# DIP2040.net
KiCad netlist of a schematic drawn in Altium Designer
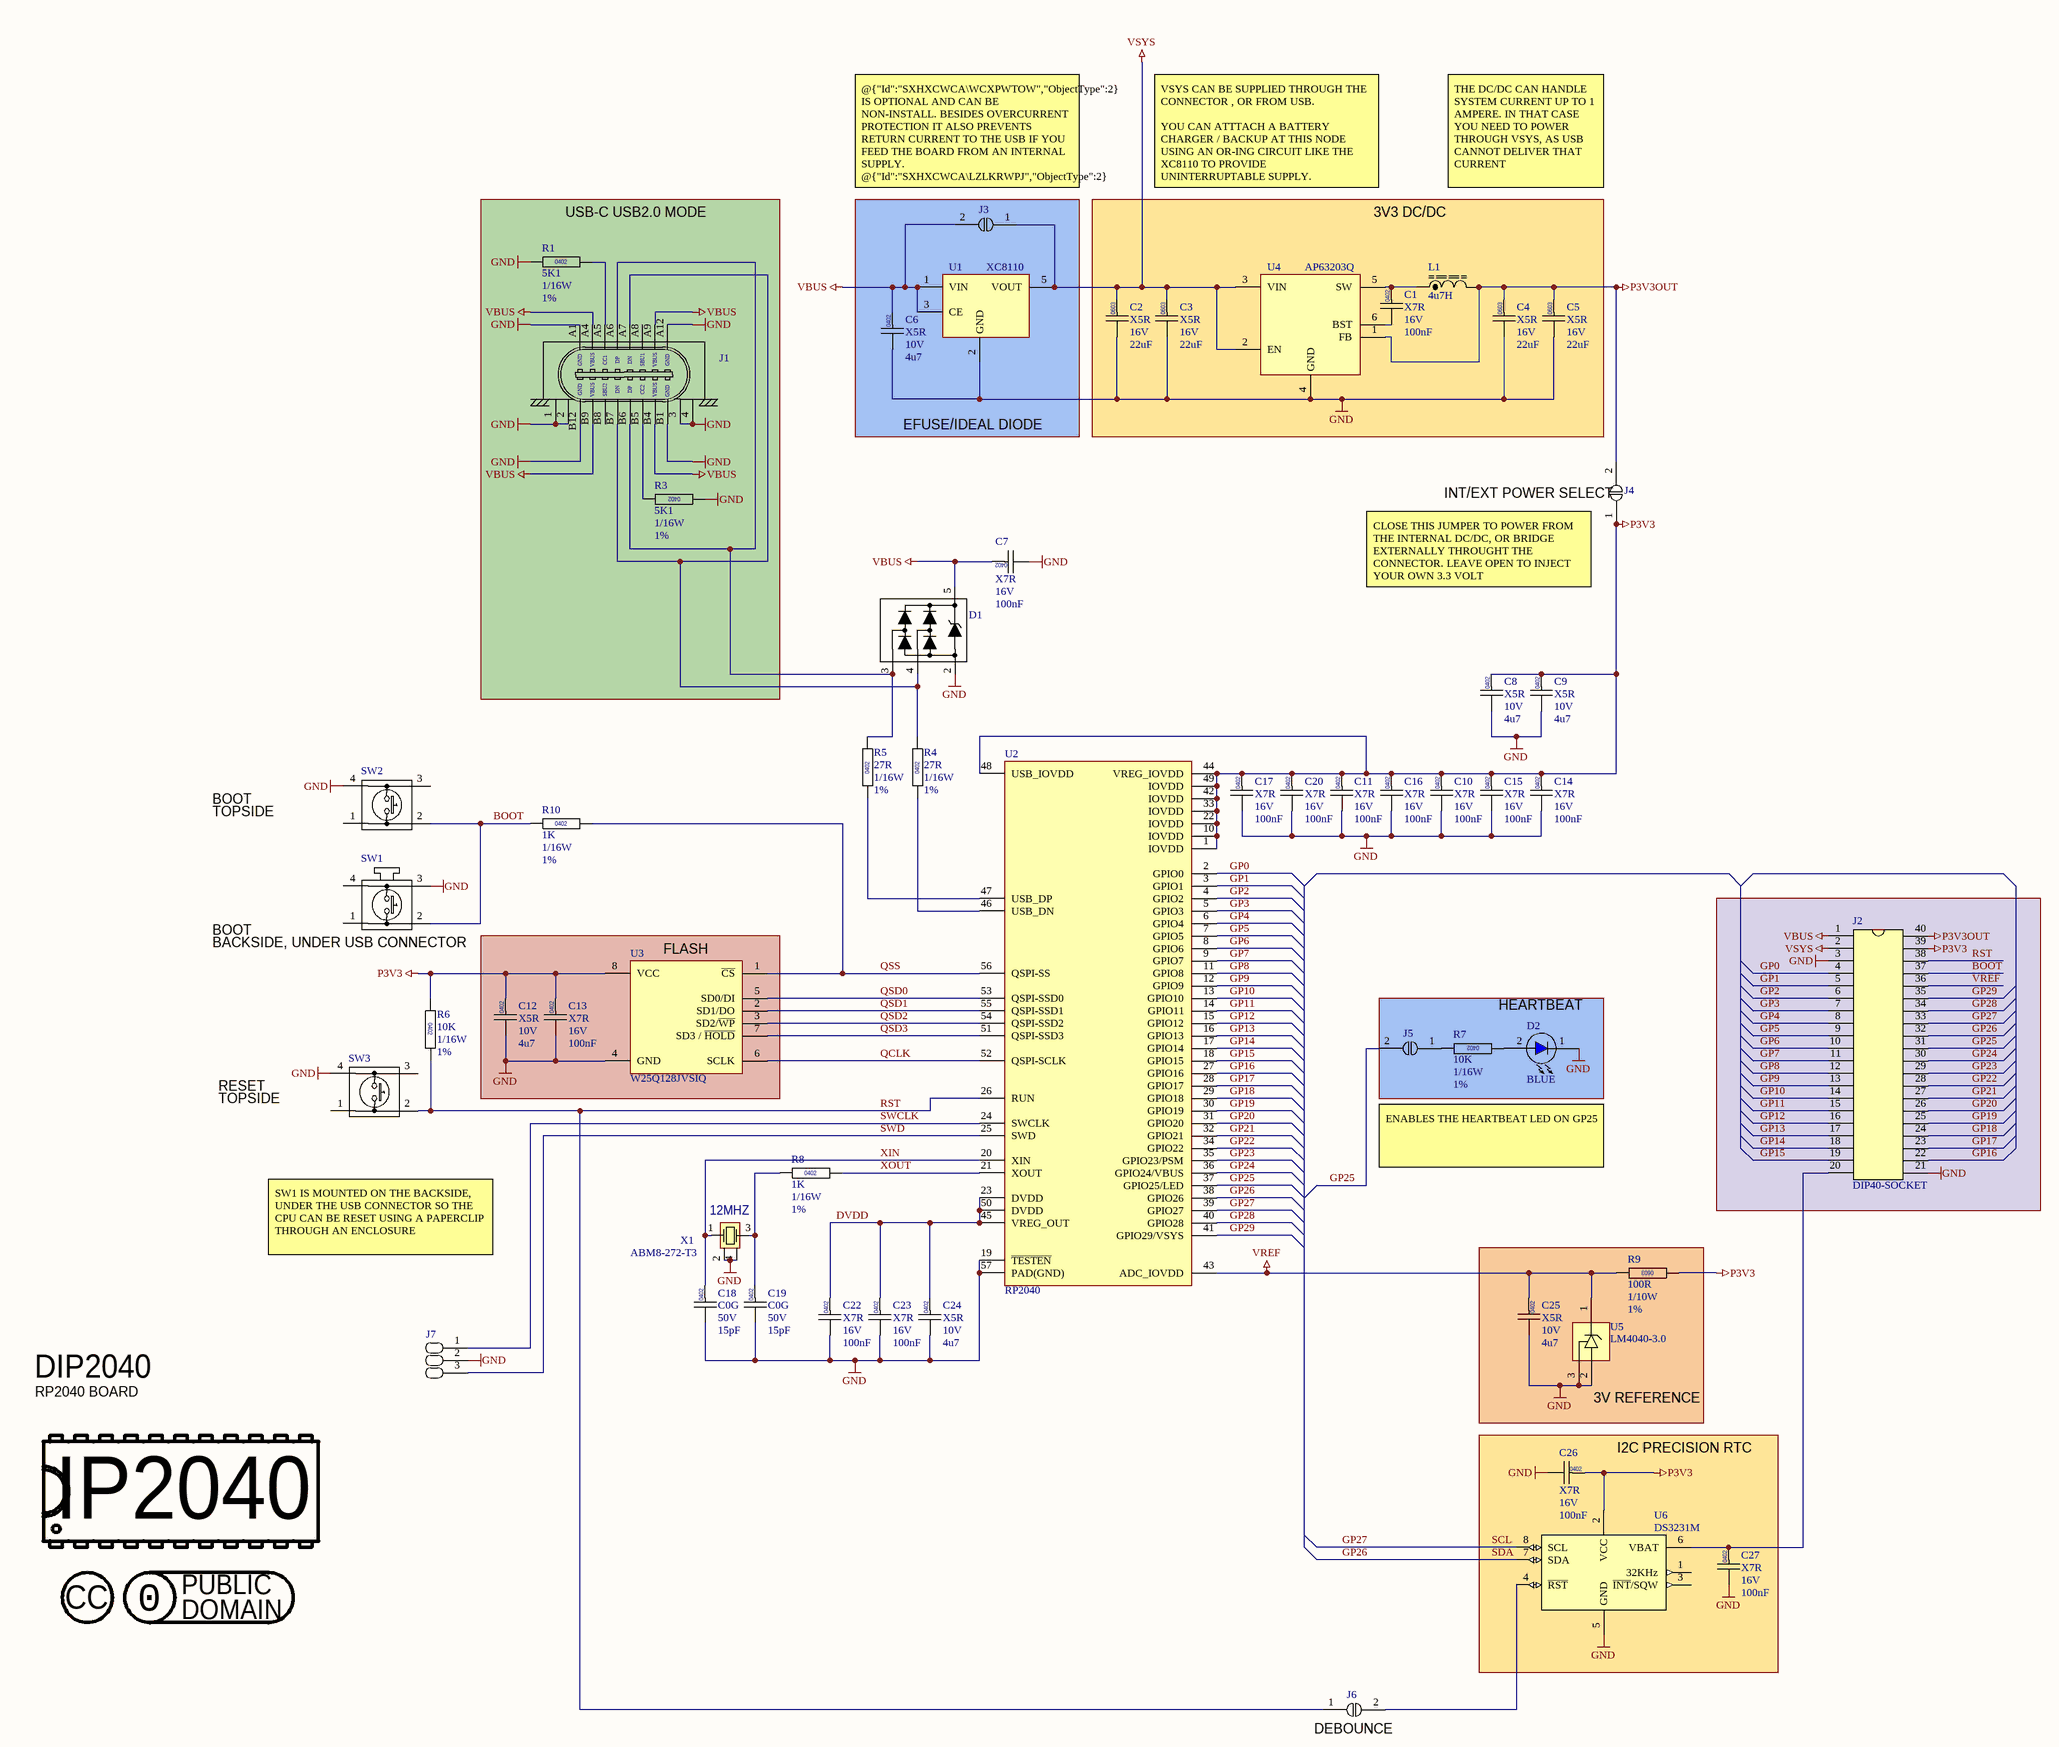
[diagram p0: DIP2040.SchDoc]

(export (version "E")
  (design (tool "Eeschema 10.0.6"))
  (components
    (comp (ref "C1")
      (value "CAP0402")
      (footprint "CAPC0402")
      (description "CAPACITOR,CERAMIC,100nF,16V,X7R,0402")
      (fields
        (field (name "DIELECTRIC") "X7R")
        (field (name "VOLTAGE") "16V")
        (field (name "CAPACITANCE") "100nF")
      )
      (libsource (lib "CAPACITORS") (part "CAPC-0402-100nF-16V-X7R"))
    )
    (comp (ref "C2")
      (value "CAP0603")
      (footprint "CAPC0603")
      (description "CAPACITOR,CERAMIC,22uF,16V,X5R,0603")
      (fields
        (field (name "DIELECTRIC") "X5R")
        (field (name "VOLTAGE") "16V")
        (field (name "CAPACITANCE") "22uF")
      )
      (libsource (lib "CAPACITORS") (part "CAPC-0603-22uF-16V-X5R"))
    )
    (comp (ref "C3")
      (value "CAP0603")
      (footprint "CAPC0603")
      (description "CAPACITOR,CERAMIC,22uF,16V,X5R,0603")
      (fields
        (field (name "DIELECTRIC") "X5R")
        (field (name "VOLTAGE") "16V")
        (field (name "CAPACITANCE") "22uF")
      )
      (libsource (lib "CAPACITORS") (part "CAPC-0603-22uF-16V-X5R"))
    )
    (comp (ref "C4")
      (value "CAP0603")
      (footprint "CAPC0603")
      (description "CAPACITOR,CERAMIC,22uF,16V,X5R,0603")
      (fields
        (field (name "DIELECTRIC") "X5R")
        (field (name "VOLTAGE") "16V")
        (field (name "CAPACITANCE") "22uF")
      )
      (libsource (lib "CAPACITORS") (part "CAPC-0603-22uF-16V-X5R"))
    )
    (comp (ref "C5")
      (value "CAP0603")
      (footprint "CAPC0603")
      (description "CAPACITOR,CERAMIC,22uF,16V,X5R,0603")
      (fields
        (field (name "DIELECTRIC") "X5R")
        (field (name "VOLTAGE") "16V")
        (field (name "CAPACITANCE") "22uF")
      )
      (libsource (lib "CAPACITORS") (part "CAPC-0603-22uF-16V-X5R"))
    )
    (comp (ref "C6")
      (value "CAP0402")
      (footprint "CAPC0402")
      (description "CAPACITOR,CERAMIC,4u7,10V,X5R,0402")
      (fields
        (field (name "DIELECTRIC") "X5R")
        (field (name "VOLTAGE") "10V")
        (field (name "CAPACITANCE") "4u7")
      )
      (libsource (lib "CAPACITORS") (part "CAPC-0402-4u7-10V-X5R"))
    )
    (comp (ref "C7")
      (value "CAP0402")
      (footprint "CAPC0402")
      (description "CAPACITOR,CERAMIC,100nF,16V,X7R,0402")
      (fields
        (field (name "DIELECTRIC") "X7R")
        (field (name "VOLTAGE") "16V")
        (field (name "CAPACITANCE") "100nF")
      )
      (libsource (lib "CAPACITORS") (part "CAPC-0402-100nF-16V-X7R"))
    )
    (comp (ref "C8")
      (value "CAP0402")
      (footprint "CAPC0402")
      (description "CAPACITOR,CERAMIC,4u7,10V,X5R,0402")
      (fields
        (field (name "DIELECTRIC") "X5R")
        (field (name "VOLTAGE") "10V")
        (field (name "CAPACITANCE") "4u7")
      )
      (libsource (lib "CAPACITORS") (part "CAPC-0402-4u7-10V-X5R"))
    )
    (comp (ref "C9")
      (value "CAP0402")
      (footprint "CAPC0402")
      (description "CAPACITOR,CERAMIC,4u7,10V,X5R,0402")
      (fields
        (field (name "DIELECTRIC") "X5R")
        (field (name "VOLTAGE") "10V")
        (field (name "CAPACITANCE") "4u7")
      )
      (libsource (lib "CAPACITORS") (part "CAPC-0402-4u7-10V-X5R"))
    )
    (comp (ref "C10")
      (value "CAP0402")
      (footprint "CAPC0402")
      (description "CAPACITOR,CERAMIC,100nF,16V,X7R,0402")
      (fields
        (field (name "DIELECTRIC") "X7R")
        (field (name "VOLTAGE") "16V")
        (field (name "CAPACITANCE") "100nF")
      )
      (libsource (lib "CAPACITORS") (part "CAPC-0402-100nF-16V-X7R"))
    )
    (comp (ref "C11")
      (value "CAP0402")
      (footprint "CAPC0402")
      (description "CAPACITOR,CERAMIC,100nF,16V,X7R,0402")
      (fields
        (field (name "DIELECTRIC") "X7R")
        (field (name "VOLTAGE") "16V")
        (field (name "CAPACITANCE") "100nF")
      )
      (libsource (lib "CAPACITORS") (part "CAPC-0402-100nF-16V-X7R"))
    )
    (comp (ref "C12")
      (value "CAP0402")
      (footprint "CAPC0402")
      (description "CAPACITOR,CERAMIC,4u7,10V,X5R,0402")
      (fields
        (field (name "DIELECTRIC") "X5R")
        (field (name "VOLTAGE") "10V")
        (field (name "CAPACITANCE") "4u7")
      )
      (libsource (lib "CAPACITORS") (part "CAPC-0402-4u7-10V-X5R"))
    )
    (comp (ref "C13")
      (value "CAP0402")
      (footprint "CAPC0402")
      (description "CAPACITOR,CERAMIC,100nF,16V,X7R,0402")
      (fields
        (field (name "DIELECTRIC") "X7R")
        (field (name "VOLTAGE") "16V")
        (field (name "CAPACITANCE") "100nF")
      )
      (libsource (lib "CAPACITORS") (part "CAPC-0402-100nF-16V-X7R"))
    )
    (comp (ref "C14")
      (value "CAP0402")
      (footprint "CAPC0402")
      (description "CAPACITOR,CERAMIC,100nF,16V,X7R,0402")
      (fields
        (field (name "DIELECTRIC") "X7R")
        (field (name "VOLTAGE") "16V")
        (field (name "CAPACITANCE") "100nF")
      )
      (libsource (lib "CAPACITORS") (part "CAPC-0402-100nF-16V-X7R"))
    )
    (comp (ref "C15")
      (value "CAP0402")
      (footprint "CAPC0402")
      (description "CAPACITOR,CERAMIC,100nF,16V,X7R,0402")
      (fields
        (field (name "DIELECTRIC") "X7R")
        (field (name "VOLTAGE") "16V")
        (field (name "CAPACITANCE") "100nF")
      )
      (libsource (lib "CAPACITORS") (part "CAPC-0402-100nF-16V-X7R"))
    )
    (comp (ref "C16")
      (value "CAP0402")
      (footprint "CAPC0402")
      (description "CAPACITOR,CERAMIC,100nF,16V,X7R,0402")
      (fields
        (field (name "DIELECTRIC") "X7R")
        (field (name "VOLTAGE") "16V")
        (field (name "CAPACITANCE") "100nF")
      )
      (libsource (lib "CAPACITORS") (part "CAPC-0402-100nF-16V-X7R"))
    )
    (comp (ref "C17")
      (value "CAP0402")
      (footprint "CAPC0402")
      (description "CAPACITOR,CERAMIC,100nF,16V,X7R,0402")
      (fields
        (field (name "DIELECTRIC") "X7R")
        (field (name "VOLTAGE") "16V")
        (field (name "CAPACITANCE") "100nF")
      )
      (libsource (lib "CAPACITORS") (part "CAPC-0402-100nF-16V-X7R"))
    )
    (comp (ref "C18")
      (value "CAP0603")
      (footprint "CAPC0402")
      (description "CAPACITOR,CERAMIC,15pF,50V,C0G,0402")
      (fields
        (field (name "DIELECTRIC") "C0G")
        (field (name "VOLTAGE") "50V")
        (field (name "CAPACITANCE") "15pF")
      )
      (libsource (lib "CAPACITORS") (part "CAPC-0402-15PF-50V-C0G"))
    )
    (comp (ref "C19")
      (value "CAP0603")
      (footprint "CAPC0402")
      (description "CAPACITOR,CERAMIC,15pF,50V,C0G,0402")
      (fields
        (field (name "DIELECTRIC") "C0G")
        (field (name "VOLTAGE") "50V")
        (field (name "CAPACITANCE") "15pF")
      )
      (libsource (lib "CAPACITORS") (part "CAPC-0402-15PF-50V-C0G"))
    )
    (comp (ref "C20")
      (value "CAP0402")
      (footprint "CAPC0402")
      (description "CAPACITOR,CERAMIC,100nF,16V,X7R,0402")
      (fields
        (field (name "DIELECTRIC") "X7R")
        (field (name "VOLTAGE") "16V")
        (field (name "CAPACITANCE") "100nF")
      )
      (libsource (lib "CAPACITORS") (part "CAPC-0402-100nF-16V-X7R"))
    )
    (comp (ref "C22")
      (value "CAP0402")
      (footprint "CAPC0402")
      (description "CAPACITOR,CERAMIC,100nF,16V,X7R,0402")
      (fields
        (field (name "DIELECTRIC") "X7R")
        (field (name "VOLTAGE") "16V")
        (field (name "CAPACITANCE") "100nF")
      )
      (libsource (lib "CAPACITORS") (part "CAPC-0402-100nF-16V-X7R"))
    )
    (comp (ref "C23")
      (value "CAP0402")
      (footprint "CAPC0402")
      (description "CAPACITOR,CERAMIC,100nF,16V,X7R,0402")
      (fields
        (field (name "DIELECTRIC") "X7R")
        (field (name "VOLTAGE") "16V")
        (field (name "CAPACITANCE") "100nF")
      )
      (libsource (lib "CAPACITORS") (part "CAPC-0402-100nF-16V-X7R"))
    )
    (comp (ref "C24")
      (value "CAP0402")
      (footprint "CAPC0402")
      (description "CAPACITOR,CERAMIC,4u7,10V,X5R,0402")
      (fields
        (field (name "DIELECTRIC") "X5R")
        (field (name "VOLTAGE") "10V")
        (field (name "CAPACITANCE") "4u7")
      )
      (libsource (lib "CAPACITORS") (part "CAPC-0402-4u7-10V-X5R"))
    )
    (comp (ref "C25")
      (value "CAP0402")
      (footprint "CAPC0402")
      (description "CAPACITOR,CERAMIC,4u7,10V,X5R,0402")
      (fields
        (field (name "DIELECTRIC") "X5R")
        (field (name "VOLTAGE") "10V")
        (field (name "CAPACITANCE") "4u7")
      )
      (libsource (lib "CAPACITORS") (part "CAPC-0402-4u7-10V-X5R"))
    )
    (comp (ref "C26")
      (value "CAP0402")
      (footprint "CAPC0402")
      (description "CAPACITOR,CERAMIC,100nF,16V,X7R,0402")
      (fields
        (field (name "DIELECTRIC") "X7R")
        (field (name "VOLTAGE") "16V")
        (field (name "CAPACITANCE") "100nF")
      )
      (libsource (lib "CAPACITORS") (part "CAPC-0402-100nF-16V-X7R"))
    )
    (comp (ref "C27")
      (value "CAP0402")
      (footprint "CAPC0402")
      (description "CAPACITOR,CERAMIC,100nF,16V,X7R,0402")
      (fields
        (field (name "DIELECTRIC") "X7R")
        (field (name "VOLTAGE") "16V")
        (field (name "CAPACITANCE") "100nF")
      )
      (libsource (lib "CAPACITORS") (part "CAPC-0402-100nF-16V-X7R"))
    )
    (comp (ref "D1")
      (value "TVS-WURTH-824011")
      (footprint "SOT23-5")
      (description "DIODE,TVS,DUAL,UNIDIRECTIONAL,USB")
      (libsource (lib "DIODES") (part "TVS-WURTH-824011"))
    )
    (comp (ref "D2")
      (value "BLUE")
      (footprint "LED-0603-BLUE")
      (description "LED,BLUE,0603")
      (libsource (lib "LED") (part "LED-WURTH-150060BS75000"))
    )
    (comp (ref "J1")
      (value "CONN-USBC-USB2-HOR")
      (footprint "CONN-GCT-USB4085")
      (description "USB-C, RIGHT ANGLE")
      (libsource (lib "CONNECTORS") (part "CONN-USBC-USB2-HOR"))
    )
    (comp (ref "J2")
      (value "DIP40-SOCKET")
      (footprint "CONN-DIP40-SOCKET")
      (libsource (lib "IC-I2C") (part "DIP40-SOCKET"))
    )
    (comp (ref "J3")
      (value "SOLDERPAD-2")
      (footprint "SOLDERPAD-2")
      (libsource (lib "BOARDFEATURES") (part "SOLDERPAD-2"))
    )
    (comp (ref "J4")
      (value "SOLDERPAD-2")
      (footprint "SOLDERPAD-2")
      (libsource (lib "BOARDFEATURES") (part "SOLDERPAD-2"))
    )
    (comp (ref "J5")
      (value "SOLDERPAD-2")
      (footprint "SOLDERPAD-2")
      (libsource (lib "BOARDFEATURES") (part "SOLDERPAD-2"))
    )
    (comp (ref "J6")
      (value "SOLDERPAD-2")
      (footprint "SOLDERPAD-2")
      (libsource (lib "BOARDFEATURES") (part "SOLDERPAD-2"))
    )
    (comp (ref "J7")
      (value "CONN-TESTPAD-1.5X1-2MMP-3")
      (footprint "CONN-TESTPAD-1.5X1-2MMP-3")
      (libsource (lib "CONNECTORS") (part "CONN-TESTPAD-1.5X1-2MMP-3"))
    )
    (comp (ref "L1")
      (value "4u7H")
      (footprint "IND-ABRACON-ASPI-3012S-3R9N-T")
      (description "IND,4.7uH,1.06A,3X3, NRH3012T4R7MN")
      (fields (field (name "Comment") "4.7uH"))
      (libsource (lib "INDUCTORS") (part "IND-TAIYO-NRH3012T4R7MN"))
    )
    (comp (ref "LOGO1")
      (value "LOGO-LICENSE-CC0-PUBLIC")
      (footprint "LOGO-LICENSE-CC0-PUBLIC")
      (libsource (lib "LOGO") (part "LOGO-LICENSE-CC0-PUBLIC"))
    )
    (comp (ref "LOGO2")
      (value "LOGO-LICENSE-CC")
      (footprint "LOGO-LICENSE-CC")
      (libsource (lib "LOGO") (part "LOGO-LICENSE-CC"))
    )
    (comp (ref "R1")
      (value "5K1")
      (footprint "RESC0402")
      (description "RESISTOR,5K1,1%,63mW,0402 (1005)")
      (fields
        (field (name "POWER") "1/16W")
        (field (name "TOLERANCE") "1%")
        (field (name "Comment") "RESC0402")
      )
      (libsource (lib "RESISTORS") (part "RESC-0402-5K1-1%-1/10W"))
    )
    (comp (ref "R3")
      (value "5K1")
      (footprint "RESC0402")
      (description "RESISTOR,5K1,1%,63mW,0402 (1005)")
      (fields
        (field (name "POWER") "1/16W")
        (field (name "TOLERANCE") "1%")
        (field (name "Comment") "RESC0402")
      )
      (libsource (lib "RESISTORS") (part "RESC-0402-5K1-1%-1/10W"))
    )
    (comp (ref "R4")
      (value "27R")
      (footprint "RESC0402")
      (description "RESISTOR,27R,1%,63mW,0402 (1005)")
      (fields
        (field (name "POWER") "1/16W")
        (field (name "TOLERANCE") "1%")
        (field (name "Comment") "RESC0402")
      )
      (libsource (lib "RESISTORS") (part "RESC-0402-27R-1%-1/10W"))
    )
    (comp (ref "R5")
      (value "27R")
      (footprint "RESC0402")
      (description "RESISTOR,27R,1%,63mW,0402 (1005)")
      (fields
        (field (name "POWER") "1/16W")
        (field (name "TOLERANCE") "1%")
        (field (name "Comment") "RESC0402")
      )
      (libsource (lib "RESISTORS") (part "RESC-0402-27R-1%-1/10W"))
    )
    (comp (ref "R6")
      (value "10K")
      (footprint "RESC0402")
      (description "RESISTOR,10K,1%,63mW,0402 (1005)")
      (fields
        (field (name "POWER") "1/16W")
        (field (name "TOLERANCE") "1%")
        (field (name "Comment") "RESC0402")
      )
      (libsource (lib "RESISTORS") (part "RESC-0402-10K-1%-1/10W"))
    )
    (comp (ref "R7")
      (value "10K")
      (footprint "RESC0402")
      (description "RESISTOR,10K,1%,63mW,0402 (1005)")
      (fields
        (field (name "POWER") "1/16W")
        (field (name "TOLERANCE") "1%")
        (field (name "Comment") "RESC0402")
      )
      (libsource (lib "RESISTORS") (part "RESC-0402-10K-1%-1/10W"))
    )
    (comp (ref "R8")
      (value "1K")
      (footprint "RESC0402")
      (description "RESISTOR,1K,1%,63mW,0402 (1005)")
      (fields
        (field (name "POWER") "1/16W")
        (field (name "TOLERANCE") "1%")
        (field (name "Comment") "RESC0402")
      )
      (libsource (lib "RESISTORS") (part "RESC-0402-1K-1%-1/10W"))
    )
    (comp (ref "R9")
      (value "100R")
      (footprint "RES0603")
      (description "RESISTOR,100R,1%,100mW,0603 (1608)")
      (fields
        (field (name "POWER") "1/10W")
        (field (name "TOLERANCE") "1%")
        (field (name "Comment") "RESC0603")
      )
      (libsource (lib "RESISTORS") (part "RESC-0603-100R-1%-1/10W"))
    )
    (comp (ref "R10")
      (value "1K")
      (footprint "RESC0402")
      (description "RESISTOR,1K,1%,63mW,0402 (1005)")
      (fields
        (field (name "POWER") "1/16W")
        (field (name "TOLERANCE") "1%")
        (field (name "Comment") "RESC0402")
      )
      (libsource (lib "RESISTORS") (part "RESC-0402-1K-1%-1/10W"))
    )
    (comp (ref "SW1")
      (value "SWITCH-E-SWITCH-TL1016")
      (footprint "SWITCH-ESWITCH-TL1016")
      (libsource (lib "SWITCH") (part "SWITCH-E-SWITCH-TL1016"))
    )
    (comp (ref "SW2")
      (value "SWITCH-PANASONIC-EVP-AA202K")
      (footprint "SWITCH-PANASONIC-EVP-AA202K")
      (libsource (lib "SWITCH") (part "SWITCH-PANASONIC-EVP-AA202K"))
    )
    (comp (ref "SW3")
      (value "SWITCH-PANASONIC-EVP-AA202K")
      (footprint "SWITCH-PANASONIC-EVP-AA202K")
      (libsource (lib "SWITCH") (part "SWITCH-PANASONIC-EVP-AA202K"))
    )
    (comp (ref "U1")
      (value "XC8110")
      (footprint "SOT23-5")
      (description "IC,PMIC,IDEAL DIODE ORING CONTROLLER")
      (libsource (lib "IC-REG") (part "IC-TOREX-XC8110"))
    )
    (comp (ref "U2")
      (value "RP2040")
      (footprint "QFN40P700X700X90-56N-TH310X310")
      (libsource (lib "IC-CPU") (part "IC-RPI-RP2040-DIP40"))
    )
    (comp (ref "U3")
      (value "W25Q128JVSIQ")
      (footprint "SO127P790-8N")
      (description "IC,FLASH,QSPI,16Mx8")
      (libsource (lib "IC-SPI") (part "IC-WINBOND-W25Q128JVSIQ"))
    )
    (comp (ref "U4")
      (value "AP63203Q")
      (footprint "SOT23-6")
      (description "IC,PMIC,STEP-DOWN, 2A 3.3V")
      (libsource (lib "IC-REG") (part "IC-DIODES-AP63203Q"))
    )
    (comp (ref "U5")
      (value "LM4040-3.0")
      (footprint "SOT23")
      (description "IC,VOLTAGE REFERENCE,3.0V")
      (libsource (lib "IC-REG") (part "IC-TI-LM4040-3"))
    )
    (comp (ref "U6")
      (value "DS3231M")
      (footprint "SO127P600-8N")
      (description "IC,RTC,I2C,DS3231M")
      (libsource (lib "IC-I2C") (part "IC-ANALOG-DS3231M"))
    )
    (comp (ref "X1")
      (value "ABM8-272-T3")
      (footprint "XTAL-ABRACON-ABM8-272-T3")
      (description "XTAL,12MHZ,RP2350")
      (libsource (lib "CRYSTALS") (part "XTAL-ABRACON-ABM8-272-T3"))
    )
  )
  (nets
    (net (code "1") (name "/BOOT") (class "Default")
      (node (ref "J2") (pin "37") (pinfunction "37_37") (pintype "passive"))
      (node (ref "R10") (pin "1") (pintype "passive"))
      (node (ref "SW1") (pin "2") (pinfunction "2_2") (pintype "passive"))
      (node (ref "SW2") (pin "2") (pinfunction "2_2") (pintype "passive"))
    )
    (net (code "2") (name "/DVDD") (class "Default")
      (node (ref "C22") (pin "1") (pintype "passive"))
      (node (ref "C23") (pin "1") (pintype "passive"))
      (node (ref "C24") (pin "1") (pintype "passive"))
      (node (ref "U2") (pin "23") (pinfunction "DVDD_23") (pintype "passive"))
      (node (ref "U2") (pin "45") (pinfunction "VREG_OUT_45") (pintype "passive"))
      (node (ref "U2") (pin "50") (pinfunction "DVDD_50") (pintype "passive"))
    )
    (net (code "3") (name "/GP0") (class "Default")
      (node (ref "J2") (pin "4") (pinfunction "4_4") (pintype "passive"))
      (node (ref "U2") (pin "2") (pinfunction "GPIO0_2") (pintype "passive"))
    )
    (net (code "4") (name "/GP1") (class "Default")
      (node (ref "J2") (pin "5") (pinfunction "5_5") (pintype "passive"))
      (node (ref "U2") (pin "3") (pinfunction "GPIO1_3") (pintype "passive"))
    )
    (net (code "5") (name "/GP2") (class "Default")
      (node (ref "J2") (pin "6") (pinfunction "6_6") (pintype "passive"))
      (node (ref "U2") (pin "4") (pinfunction "GPIO2_4") (pintype "passive"))
    )
    (net (code "6") (name "/GP3") (class "Default")
      (node (ref "J2") (pin "7") (pinfunction "7_7") (pintype "passive"))
      (node (ref "U2") (pin "5") (pinfunction "GPIO3_5") (pintype "passive"))
    )
    (net (code "7") (name "/GP4") (class "Default")
      (node (ref "J2") (pin "8") (pinfunction "8_8") (pintype "passive"))
      (node (ref "U2") (pin "6") (pinfunction "GPIO4_6") (pintype "passive"))
    )
    (net (code "8") (name "/GP5") (class "Default")
      (node (ref "J2") (pin "9") (pinfunction "9_9") (pintype "passive"))
      (node (ref "U2") (pin "7") (pinfunction "GPIO5_7") (pintype "passive"))
    )
    (net (code "9") (name "/GP6") (class "Default")
      (node (ref "J2") (pin "10") (pinfunction "10_10") (pintype "passive"))
      (node (ref "U2") (pin "8") (pinfunction "GPIO6_8") (pintype "passive"))
    )
    (net (code "10") (name "/GP7") (class "Default")
      (node (ref "J2") (pin "11") (pinfunction "11_11") (pintype "passive"))
      (node (ref "U2") (pin "9") (pinfunction "GPIO7_9") (pintype "passive"))
    )
    (net (code "11") (name "/GP8") (class "Default")
      (node (ref "J2") (pin "12") (pinfunction "12_12") (pintype "passive"))
      (node (ref "U2") (pin "11") (pinfunction "GPIO8_11") (pintype "passive"))
    )
    (net (code "12") (name "/GP9") (class "Default")
      (node (ref "J2") (pin "13") (pinfunction "13_13") (pintype "passive"))
      (node (ref "U2") (pin "12") (pinfunction "GPIO9_12") (pintype "passive"))
    )
    (net (code "13") (name "/GP10") (class "Default")
      (node (ref "J2") (pin "14") (pinfunction "14_14") (pintype "passive"))
      (node (ref "U2") (pin "13") (pinfunction "GPIO10_13") (pintype "passive"))
    )
    (net (code "14") (name "/GP11") (class "Default")
      (node (ref "J2") (pin "15") (pinfunction "15_15") (pintype "passive"))
      (node (ref "U2") (pin "14") (pinfunction "GPIO11_14") (pintype "passive"))
    )
    (net (code "15") (name "/GP12") (class "Default")
      (node (ref "J2") (pin "16") (pinfunction "16_16") (pintype "passive"))
      (node (ref "U2") (pin "15") (pinfunction "GPIO12_15") (pintype "passive"))
    )
    (net (code "16") (name "/GP13") (class "Default")
      (node (ref "J2") (pin "17") (pinfunction "17_17") (pintype "passive"))
      (node (ref "U2") (pin "16") (pinfunction "GPIO13_16") (pintype "passive"))
    )
    (net (code "17") (name "/GP14") (class "Default")
      (node (ref "J2") (pin "18") (pinfunction "18_18") (pintype "passive"))
      (node (ref "U2") (pin "17") (pinfunction "GPIO14_17") (pintype "passive"))
    )
    (net (code "18") (name "/GP15") (class "Default")
      (node (ref "J2") (pin "19") (pinfunction "19_19") (pintype "passive"))
      (node (ref "U2") (pin "18") (pinfunction "GPIO15_18") (pintype "passive"))
    )
    (net (code "19") (name "/GP16") (class "Default")
      (node (ref "J2") (pin "22") (pinfunction "22_22") (pintype "passive"))
      (node (ref "U2") (pin "27") (pinfunction "GPIO16_27") (pintype "passive"))
    )
    (net (code "20") (name "/GP17") (class "Default")
      (node (ref "J2") (pin "23") (pinfunction "23_23") (pintype "passive"))
      (node (ref "U2") (pin "28") (pinfunction "GPIO17_28") (pintype "passive"))
    )
    (net (code "21") (name "/GP18") (class "Default")
      (node (ref "J2") (pin "24") (pinfunction "24_24") (pintype "passive"))
      (node (ref "U2") (pin "29") (pinfunction "GPIO18_29") (pintype "passive"))
    )
    (net (code "22") (name "/GP19") (class "Default")
      (node (ref "J2") (pin "25") (pinfunction "25_25") (pintype "passive"))
      (node (ref "U2") (pin "30") (pinfunction "GPIO19_30") (pintype "passive"))
    )
    (net (code "23") (name "/GP20") (class "Default")
      (node (ref "J2") (pin "26") (pinfunction "26_26") (pintype "passive"))
      (node (ref "U2") (pin "31") (pinfunction "GPIO20_31") (pintype "passive"))
    )
    (net (code "24") (name "/GP21") (class "Default")
      (node (ref "J2") (pin "27") (pinfunction "27_27") (pintype "passive"))
      (node (ref "U2") (pin "32") (pinfunction "GPIO21_32") (pintype "passive"))
    )
    (net (code "25") (name "/GP22") (class "Default")
      (node (ref "J2") (pin "28") (pinfunction "28_28") (pintype "passive"))
      (node (ref "U2") (pin "34") (pinfunction "GPIO22_34") (pintype "passive"))
    )
    (net (code "26") (name "/GP23") (class "Default")
      (node (ref "J2") (pin "29") (pinfunction "29_29") (pintype "passive"))
      (node (ref "U2") (pin "35") (pinfunction "GPIO23/PSM_35") (pintype "passive"))
    )
    (net (code "27") (name "/GP24") (class "Default")
      (node (ref "J2") (pin "30") (pinfunction "30_30") (pintype "passive"))
      (node (ref "U2") (pin "36") (pinfunction "GPIO24/VBUS_36") (pintype "passive"))
    )
    (net (code "28") (name "/GP25") (class "Default")
      (node (ref "J2") (pin "31") (pinfunction "31_31") (pintype "passive"))
      (node (ref "J5") (pin "2") (pinfunction "2_2") (pintype "passive"))
      (node (ref "U2") (pin "37") (pinfunction "GPIO25/LED_37") (pintype "passive"))
    )
    (net (code "29") (name "/GP26") (class "Default")
      (node (ref "J2") (pin "32") (pinfunction "32_32") (pintype "passive"))
      (node (ref "U2") (pin "38") (pinfunction "GPIO26_38") (pintype "passive"))
      (node (ref "U6") (pin "7") (pinfunction "SDA_7") (pintype "bidirectional"))
    )
    (net (code "30") (name "/GP27") (class "Default")
      (node (ref "J2") (pin "33") (pinfunction "33_33") (pintype "passive"))
      (node (ref "U2") (pin "39") (pinfunction "GPIO27_39") (pintype "passive"))
      (node (ref "U6") (pin "8") (pinfunction "SCL_8") (pintype "bidirectional"))
    )
    (net (code "31") (name "/GP28") (class "Default")
      (node (ref "J2") (pin "34") (pinfunction "34_34") (pintype "passive"))
      (node (ref "U2") (pin "40") (pinfunction "GPIO28_40") (pintype "passive"))
    )
    (net (code "32") (name "/GP29") (class "Default")
      (node (ref "J2") (pin "35") (pinfunction "35_35") (pintype "passive"))
      (node (ref "U2") (pin "41") (pinfunction "GPIO29/VSYS_41") (pintype "passive"))
    )
    (net (code "33") (name "/QCLK") (class "Default")
      (node (ref "U2") (pin "52") (pinfunction "QSPI-SCLK_52") (pintype "passive"))
      (node (ref "U3") (pin "6") (pinfunction "SCLK_6") (pintype "passive"))
    )
    (net (code "34") (name "/QSD0") (class "Default")
      (node (ref "U2") (pin "53") (pinfunction "QSPI-SSD0_53") (pintype "passive"))
      (node (ref "U3") (pin "5") (pinfunction "SD0/DI_5") (pintype "passive"))
    )
    (net (code "35") (name "/QSD1") (class "Default")
      (node (ref "U2") (pin "55") (pinfunction "QSPI-SSD1_55") (pintype "passive"))
      (node (ref "U3") (pin "2") (pinfunction "SD1/DO_2") (pintype "passive"))
    )
    (net (code "36") (name "/QSD2") (class "Default")
      (node (ref "U2") (pin "54") (pinfunction "QSPI-SSD2_54") (pintype "passive"))
      (node (ref "U3") (pin "3") (pinfunction "SD2/~{WP}_3") (pintype "passive"))
    )
    (net (code "37") (name "/QSD3") (class "Default")
      (node (ref "U2") (pin "51") (pinfunction "QSPI-SSD3_51") (pintype "passive"))
      (node (ref "U3") (pin "7") (pinfunction "SD3_/_~{HOLD}_7") (pintype "passive"))
    )
    (net (code "38") (name "/QSS") (class "Default")
      (node (ref "R10") (pin "2") (pintype "passive"))
      (node (ref "U2") (pin "56") (pinfunction "QSPI-SS_56") (pintype "passive"))
      (node (ref "U3") (pin "1") (pinfunction "~{CS}_1") (pintype "passive"))
    )
    (net (code "39") (name "/RST") (class "Default")
      (node (ref "J2") (pin "38") (pinfunction "38_38") (pintype "passive"))
      (node (ref "J6") (pin "1") (pinfunction "1_1") (pintype "passive"))
      (node (ref "R6") (pin "1") (pintype "passive"))
      (node (ref "SW3") (pin "2") (pinfunction "2_2") (pintype "passive"))
      (node (ref "U2") (pin "26") (pinfunction "RUN_26") (pintype "passive"))
    )
    (net (code "40") (name "/SWCLK") (class "Default")
      (node (ref "J7") (pin "1") (pinfunction "1_1") (pintype "passive"))
      (node (ref "U2") (pin "24") (pinfunction "SWCLK_24") (pintype "passive"))
    )
    (net (code "41") (name "/SWD") (class "Default")
      (node (ref "J7") (pin "3") (pinfunction "3_3") (pintype "passive"))
      (node (ref "U2") (pin "25") (pinfunction "SWD_25") (pintype "passive"))
    )
    (net (code "42") (name "/XIN") (class "Default")
      (node (ref "C18") (pin "1") (pintype "passive"))
      (node (ref "U2") (pin "20") (pinfunction "XIN_20") (pintype "passive"))
      (node (ref "X1") (pin "1") (pinfunction "1_1") (pintype "passive"))
    )
    (net (code "43") (name "/XOUT") (class "Default")
      (node (ref "R8") (pin "2") (pintype "passive"))
      (node (ref "U2") (pin "21") (pinfunction "XOUT_21") (pintype "passive"))
    )
    (net (code "44") (name "GND") (class "Default")
      (node (ref "C10") (pin "2") (pintype "passive"))
      (node (ref "C11") (pin "2") (pintype "passive"))
      (node (ref "C12") (pin "2") (pintype "passive"))
      (node (ref "C13") (pin "2") (pintype "passive"))
      (node (ref "C14") (pin "2") (pintype "passive"))
      (node (ref "C15") (pin "2") (pintype "passive"))
      (node (ref "C16") (pin "2") (pintype "passive"))
      (node (ref "C17") (pin "2") (pintype "passive"))
      (node (ref "C18") (pin "2") (pintype "passive"))
      (node (ref "C19") (pin "2") (pintype "passive"))
      (node (ref "C2") (pin "2") (pintype "passive"))
      (node (ref "C20") (pin "2") (pintype "passive"))
      (node (ref "C22") (pin "2") (pintype "passive"))
      (node (ref "C23") (pin "2") (pintype "passive"))
      (node (ref "C24") (pin "2") (pintype "passive"))
      (node (ref "C25") (pin "2") (pintype "passive"))
      (node (ref "C26") (pin "2") (pintype "passive"))
      (node (ref "C27") (pin "2") (pintype "passive"))
      (node (ref "C3") (pin "2") (pintype "passive"))
      (node (ref "C4") (pin "2") (pintype "passive"))
      (node (ref "C5") (pin "2") (pintype "passive"))
      (node (ref "C6") (pin "2") (pintype "passive"))
      (node (ref "C7") (pin "2") (pintype "passive"))
      (node (ref "C8") (pin "2") (pintype "passive"))
      (node (ref "C9") (pin "2") (pintype "passive"))
      (node (ref "D1") (pin "2") (pinfunction "A_2") (pintype "passive"))
      (node (ref "D2") (pin "1") (pinfunction "A_1") (pintype "passive"))
      (node (ref "J1") (pin "1") (pinfunction "1_1") (pintype "passive"))
      (node (ref "J1") (pin "2") (pinfunction "2_2") (pintype "passive"))
      (node (ref "J1") (pin "3") (pinfunction "3_3") (pintype "passive"))
      (node (ref "J1") (pin "4") (pinfunction "4_4") (pintype "passive"))
      (node (ref "J1") (pin "A1") (pinfunction "A1_A1") (pintype "passive"))
      (node (ref "J1") (pin "A12") (pinfunction "A12_A12") (pintype "passive"))
      (node (ref "J1") (pin "B1") (pinfunction "B1_B1") (pintype "passive"))
      (node (ref "J1") (pin "B12") (pinfunction "B12_B12") (pintype "passive"))
      (node (ref "J2") (pin "21") (pinfunction "21_21") (pintype "passive"))
      (node (ref "J2") (pin "3") (pinfunction "3_3") (pintype "passive"))
      (node (ref "J7") (pin "2") (pinfunction "2_2") (pintype "passive"))
      (node (ref "R1") (pin "2") (pintype "passive"))
      (node (ref "R3") (pin "2") (pintype "passive"))
      (node (ref "SW1") (pin "3") (pinfunction "3_3") (pintype "passive"))
      (node (ref "SW2") (pin "4") (pinfunction "4_4") (pintype "passive"))
      (node (ref "SW3") (pin "4") (pinfunction "4_4") (pintype "passive"))
      (node (ref "U1") (pin "2") (pinfunction "GND_2") (pintype "passive"))
      (node (ref "U2") (pin "19") (pinfunction "~{TESTEN}_19") (pintype "passive"))
      (node (ref "U2") (pin "57") (pinfunction "PAD(GND)_57") (pintype "passive"))
      (node (ref "U3") (pin "4") (pinfunction "GND_4") (pintype "passive"))
      (node (ref "U4") (pin "4") (pinfunction "GND_4") (pintype "passive"))
      (node (ref "U5") (pin "2") (pinfunction "2_2") (pintype "passive"))
      (node (ref "U5") (pin "3") (pinfunction "3_3") (pintype "passive"))
      (node (ref "U6") (pin "5") (pinfunction "GND_5") (pintype "power_in"))
      (node (ref "X1") (pin "2") (pinfunction "2_2") (pintype "passive"))
      (node (ref "X1") (pin "4") (pinfunction "4_4") (pintype "passive"))
    )
    (net (code "45") (name "Net-(C19-Pad1)") (class "Default")
      (node (ref "C19") (pin "1") (pintype "passive"))
      (node (ref "R8") (pin "1") (pintype "passive"))
      (node (ref "X1") (pin "3") (pinfunction "3_3") (pintype "passive"))
    )
    (net (code "46") (name "Net-(D1-A-Pad3)") (class "Default")
      (node (ref "D1") (pin "3") (pinfunction "A_3") (pintype "passive"))
      (node (ref "J1") (pin "A6") (pinfunction "A6_A6") (pintype "passive"))
      (node (ref "J1") (pin "B6") (pinfunction "B6_B6") (pintype "passive"))
      (node (ref "R5") (pin "1") (pintype "passive"))
    )
    (net (code "47") (name "Net-(D1-A-Pad4)") (class "Default")
      (node (ref "D1") (pin "4") (pinfunction "A_4") (pintype "passive"))
      (node (ref "J1") (pin "A7") (pinfunction "A7_A7") (pintype "passive"))
      (node (ref "J1") (pin "B7") (pinfunction "B7_B7") (pintype "passive"))
      (node (ref "R4") (pin "1") (pintype "passive"))
    )
    (net (code "48") (name "Net-(D2-K)") (class "Default")
      (node (ref "D2") (pin "2") (pinfunction "K_2") (pintype "passive"))
      (node (ref "R7") (pin "2") (pintype "passive"))
    )
    (net (code "49") (name "Net-(J1-PadA5)") (class "Default")
      (node (ref "J1") (pin "A5") (pinfunction "A5_A5") (pintype "passive"))
      (node (ref "R1") (pin "1") (pintype "passive"))
    )
    (net (code "50") (name "Net-(J1-PadB5)") (class "Default")
      (node (ref "J1") (pin "B5") (pinfunction "B5_B5") (pintype "passive"))
      (node (ref "R3") (pin "1") (pintype "passive"))
    )
    (net (code "51") (name "Net-(J5-Pad1)") (class "Default")
      (node (ref "J5") (pin "1") (pinfunction "1_1") (pintype "passive"))
      (node (ref "R7") (pin "1") (pintype "passive"))
    )
    (net (code "52") (name "Net-(U2-USB_DN)") (class "Default")
      (node (ref "R4") (pin "2") (pintype "passive"))
      (node (ref "U2") (pin "46") (pinfunction "USB_DN_46") (pintype "passive"))
    )
    (net (code "53") (name "Net-(U2-USB_DP)") (class "Default")
      (node (ref "R5") (pin "2") (pintype "passive"))
      (node (ref "U2") (pin "47") (pinfunction "USB_DP_47") (pintype "passive"))
    )
    (net (code "54") (name "Net-(U4-BST)") (class "Default")
      (node (ref "C1") (pin "2") (pintype "passive"))
      (node (ref "U4") (pin "6") (pinfunction "BST_6") (pintype "passive"))
    )
    (net (code "55") (name "Net-(U4-SW)") (class "Default")
      (node (ref "C1") (pin "1") (pintype "passive"))
      (node (ref "L1") (pin "1") (pinfunction "1_1") (pintype "passive"))
      (node (ref "U4") (pin "5") (pinfunction "SW_5") (pintype "passive"))
    )
    (net (code "56") (name "Net-(U6-VBAT)") (class "Default")
      (node (ref "C27") (pin "1") (pintype "passive"))
      (node (ref "J2") (pin "20") (pinfunction "20_20") (pintype "passive"))
      (node (ref "U6") (pin "6") (pinfunction "VBAT_6") (pintype "passive"))
    )
    (net (code "57") (name "Net-(U6-~{RST})") (class "Default")
      (node (ref "J6") (pin "2") (pinfunction "2_2") (pintype "passive"))
      (node (ref "U6") (pin "4") (pinfunction "~{RST}_4") (pintype "bidirectional"))
    )
    (net (code "58") (name "P3V3") (class "Default")
      (node (ref "C10") (pin "1") (pintype "passive"))
      (node (ref "C11") (pin "1") (pintype "passive"))
      (node (ref "C12") (pin "1") (pintype "passive"))
      (node (ref "C13") (pin "1") (pintype "passive"))
      (node (ref "C14") (pin "1") (pintype "passive"))
      (node (ref "C15") (pin "1") (pintype "passive"))
      (node (ref "C16") (pin "1") (pintype "passive"))
      (node (ref "C17") (pin "1") (pintype "passive"))
      (node (ref "C20") (pin "1") (pintype "passive"))
      (node (ref "C26") (pin "1") (pintype "passive"))
      (node (ref "C8") (pin "1") (pintype "passive"))
      (node (ref "C9") (pin "1") (pintype "passive"))
      (node (ref "J2") (pin "39") (pinfunction "39_39") (pintype "passive"))
      (node (ref "J4") (pin "1") (pinfunction "1_1") (pintype "passive"))
      (node (ref "R6") (pin "2") (pintype "passive"))
      (node (ref "R9") (pin "2") (pintype "passive"))
      (node (ref "U2") (pin "1") (pinfunction "IOVDD_1") (pintype "passive"))
      (node (ref "U2") (pin "10") (pinfunction "IOVDD_10") (pintype "passive"))
      (node (ref "U2") (pin "22") (pinfunction "IOVDD_22") (pintype "passive"))
      (node (ref "U2") (pin "33") (pinfunction "IOVDD_33") (pintype "passive"))
      (node (ref "U2") (pin "42") (pinfunction "IOVDD_42") (pintype "passive"))
      (node (ref "U2") (pin "44") (pinfunction "VREG_IOVDD_44") (pintype "passive"))
      (node (ref "U2") (pin "48") (pinfunction "USB_IOVDD_48") (pintype "passive"))
      (node (ref "U2") (pin "49") (pinfunction "IOVDD_49") (pintype "passive"))
      (node (ref "U3") (pin "8") (pinfunction "VCC_8") (pintype "passive"))
      (node (ref "U6") (pin "2") (pinfunction "VCC_2") (pintype "passive"))
    )
    (net (code "59") (name "P3V3OUT") (class "Default")
      (node (ref "C4") (pin "1") (pintype "passive"))
      (node (ref "C5") (pin "1") (pintype "passive"))
      (node (ref "J2") (pin "40") (pinfunction "40_40") (pintype "passive"))
      (node (ref "J4") (pin "2") (pinfunction "2_2") (pintype "passive"))
      (node (ref "L1") (pin "2") (pinfunction "2_2") (pintype "passive"))
      (node (ref "U4") (pin "1") (pinfunction "FB_1") (pintype "passive"))
    )
    (net (code "60") (name "VBUS") (class "Default")
      (node (ref "C6") (pin "1") (pintype "passive"))
      (node (ref "C7") (pin "1") (pintype "passive"))
      (node (ref "D1") (pin "5") (pinfunction "A_5") (pintype "passive"))
      (node (ref "J1") (pin "A4") (pinfunction "A4_A4") (pintype "passive"))
      (node (ref "J1") (pin "A9") (pinfunction "A9_A9") (pintype "passive"))
      (node (ref "J1") (pin "B4") (pinfunction "B4_B4") (pintype "passive"))
      (node (ref "J1") (pin "B9") (pinfunction "B9_B9") (pintype "passive"))
      (node (ref "J2") (pin "1") (pinfunction "1_1") (pintype "passive"))
      (node (ref "J3") (pin "2") (pinfunction "2_2") (pintype "passive"))
      (node (ref "U1") (pin "1") (pinfunction "VIN_1") (pintype "passive"))
      (node (ref "U1") (pin "3") (pinfunction "CE_3") (pintype "passive"))
    )
    (net (code "61") (name "VREF") (class "Default")
      (node (ref "C25") (pin "1") (pintype "passive"))
      (node (ref "J2") (pin "36") (pinfunction "36_36") (pintype "passive"))
      (node (ref "R9") (pin "1") (pintype "passive"))
      (node (ref "U2") (pin "43") (pinfunction "ADC_IOVDD_43") (pintype "passive"))
      (node (ref "U5") (pin "1") (pinfunction "1_1") (pintype "passive"))
    )
    (net (code "62") (name "VSYS") (class "Default")
      (node (ref "C2") (pin "1") (pintype "passive"))
      (node (ref "C3") (pin "1") (pintype "passive"))
      (node (ref "J2") (pin "2") (pinfunction "2_2") (pintype "passive"))
      (node (ref "J3") (pin "1") (pinfunction "1_1") (pintype "passive"))
      (node (ref "U1") (pin "5") (pinfunction "VOUT_5") (pintype "passive"))
      (node (ref "U4") (pin "2") (pinfunction "EN_2") (pintype "passive"))
      (node (ref "U4") (pin "3") (pinfunction "VIN_3") (pintype "passive"))
    )
    (net (code "63") (name "unconnected-(J1-PadA8)") (class "Default")
      (node (ref "J1") (pin "A8") (pinfunction "A8_A8") (pintype "passive"))
    )
    (net (code "64") (name "unconnected-(J1-PadB8)") (class "Default")
      (node (ref "J1") (pin "B8") (pinfunction "B8_B8") (pintype "passive"))
    )
    (net (code "65") (name "unconnected-(SW1-Pad1)") (class "Default")
      (node (ref "SW1") (pin "1") (pinfunction "1_1") (pintype "passive"))
    )
    (net (code "66") (name "unconnected-(SW1-Pad4)") (class "Default")
      (node (ref "SW1") (pin "4") (pinfunction "4_4") (pintype "passive"))
    )
    (net (code "67") (name "unconnected-(SW2-Pad1)") (class "Default")
      (node (ref "SW2") (pin "1") (pinfunction "1_1") (pintype "passive"))
    )
    (net (code "68") (name "unconnected-(SW2-Pad3)") (class "Default")
      (node (ref "SW2") (pin "3") (pinfunction "3_3") (pintype "passive"))
    )
    (net (code "69") (name "unconnected-(SW3-Pad1)") (class "Default")
      (node (ref "SW3") (pin "1") (pinfunction "1_1") (pintype "passive"))
    )
    (net (code "70") (name "unconnected-(SW3-Pad3)") (class "Default")
      (node (ref "SW3") (pin "3") (pinfunction "3_3") (pintype "passive"))
    )
    (net (code "71") (name "unconnected-(U6-32KHz-Pad1)") (class "Default")
      (node (ref "U6") (pin "1") (pinfunction "32KHz_1") (pintype "output"))
    )
    (net (code "72") (name "unconnected-(U6-~{INT}{slash}SQW-Pad3)") (class "Default")
      (node (ref "U6") (pin "3") (pinfunction "~{INT}/SQW_3") (pintype "output"))
    )
  )
)
